# leo_SBM_BUCK.net
KiCad netlist of a schematic drawn in Altium Designer
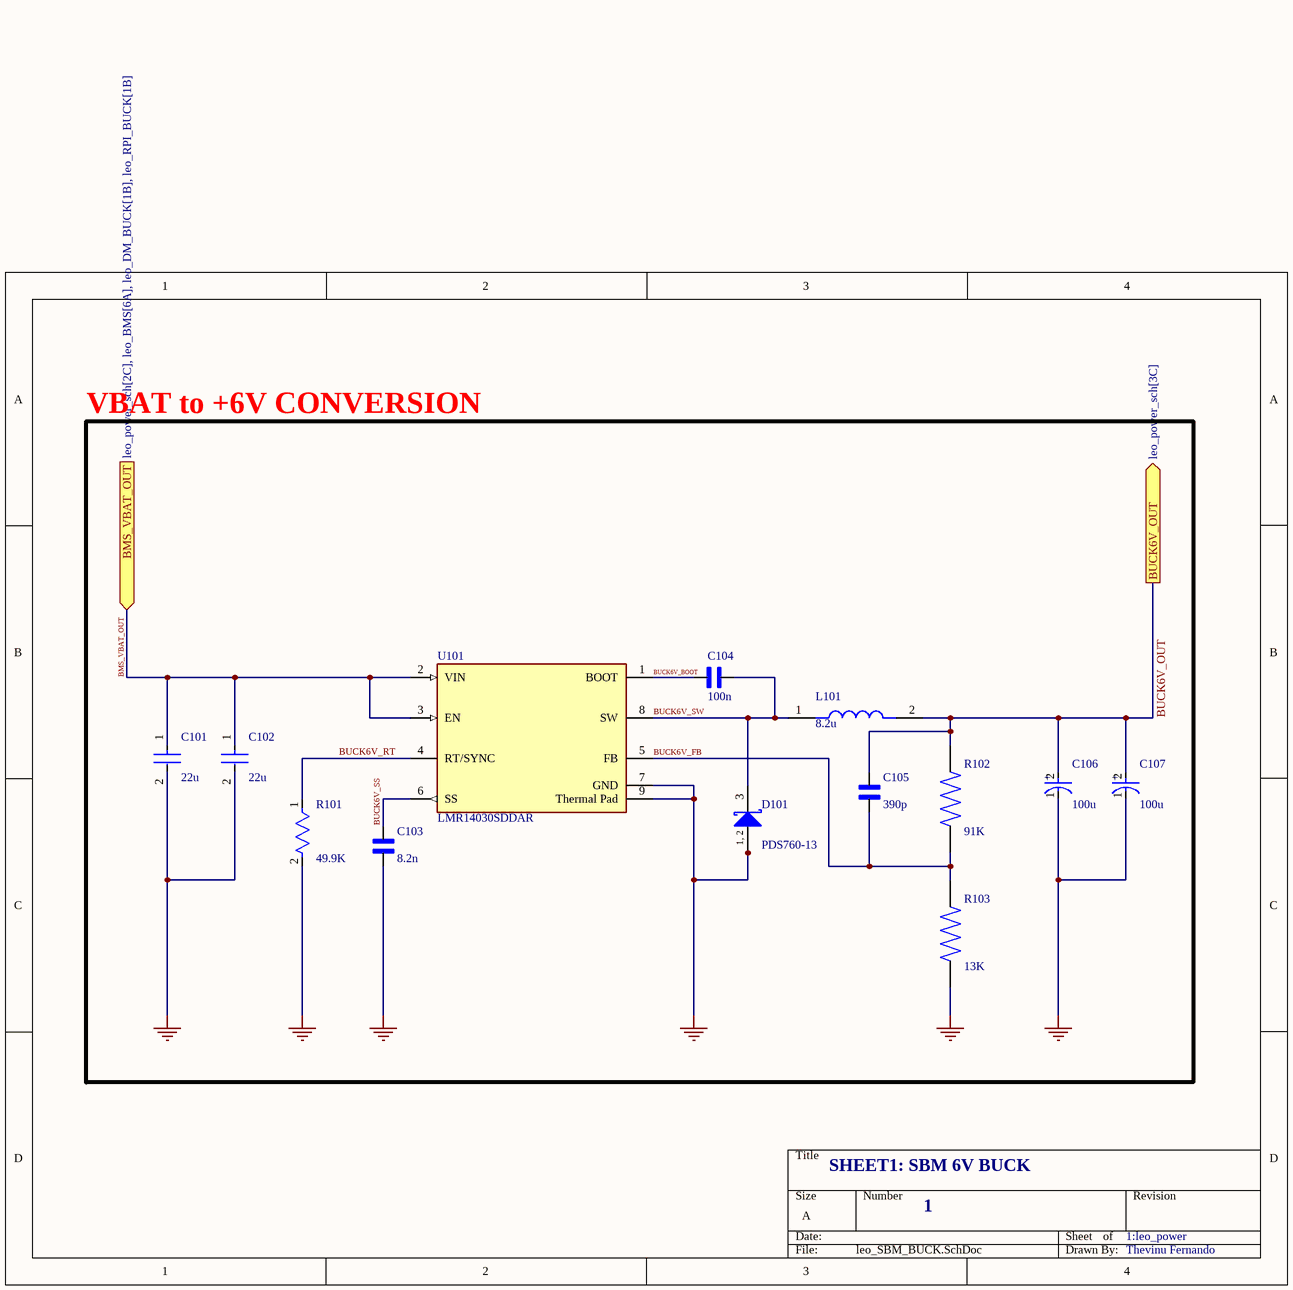
[diagram p0: leo_SBM_BUCK.SchDoc]

(export (version "E")
  (design (tool "Eeschema 10.0.6"))
  (components
    (comp (ref "C101")
      (value "22u")
      (footprint "CAP_1206")
      (fields
        (field (name "MOUSER PART NUMBER") "187-CL31A226KAHNNNE")
        (field (name "PART NUMBER") "CL31A226KAHNNNE")
        (field (name "DIGIKEY PART NUMBER") "1276-3047-1-ND")
      )
      (libsource (lib "leo_power_schlib") (part "CAP_1206"))
    )
    (comp (ref "C102")
      (value "22u")
      (footprint "CAP_1206")
      (fields
        (field (name "MOUSER PART NUMBER") "187-CL31A226KAHNNNE")
        (field (name "PART NUMBER") "CL31A226KAHNNNE")
        (field (name "DIGIKEY PART NUMBER") "1276-3047-1-ND")
      )
      (libsource (lib "leo_power_schlib") (part "CAP_1206"))
    )
    (comp (ref "C103")
      (value "8.2n")
      (footprint "CAP_0402")
      (description "±10% 50V Ceramic Capacitor X7R 0402")
      (fields (field (name "MF") "Samsung") (field (name "MP") "CL05B104KO5NNNC"))
      (libsource (lib "") (part "CAP_0402_1"))
    )
    (comp (ref "C104")
      (value "100n")
      (footprint "CAP_0402")
      (description "±10% 50V Ceramic Capacitor X7R 0402")
      (fields (field (name "MF") "Samsung") (field (name "MP") "CL05B104KO5NNNC"))
      (libsource (lib "leo_power_schlib") (part "CAP_0402"))
    )
    (comp (ref "C105")
      (value "390p")
      (footprint "CAP_0402")
      (description "±10% 50V Ceramic Capacitor X7R 0402")
      (fields (field (name "MF") "Samsung") (field (name "MP") "CL05B104KO5NNNC"))
      (libsource (lib "") (part "CAP_0402_1"))
    )
    (comp (ref "C106")
      (value "100u")
      (footprint "FP-OS-CON-SMT-C6-MFG")
      (description "100uF ±20% 16V Aluminum - Polymer Capacitors SMD,D6.3xL5.9mm 2000hrs@105℃")
      (fields (field (name "VOLTAGE") "16V") (field (name "TOLERANCE") "20%"))
      (libsource (lib "leo_power_schlib") (part "16SVPC100M"))
    )
    (comp (ref "C107")
      (value "100u")
      (footprint "FP-OS-CON-SMT-C6-MFG")
      (description "100uF ±20% 16V Aluminum - Polymer Capacitors SMD,D6.3xL5.9mm 2000hrs@105℃")
      (fields (field (name "VOLTAGE") "16V") (field (name "TOLERANCE") "20%"))
      (libsource (lib "leo_power_schlib") (part "16SVPC100M"))
    )
    (comp (ref "D101")
      (value "PDS760-13")
      (footprint "DIOD-POWERDI5-3_V")
      (description "Schottky Barrier Rectifier, 60 V, 7 A, -65 to 150 degC, 3-Pin SMD, RoHS, Tape and Reel")
      (fields (field (name "MANUFACTURER") "Diodes Inc"))
      (libsource (lib "leo_power_schlib") (part "PDS760-13"))
    )
    (comp (ref "L101")
      (value "8.2u")
      (footprint "IND_104CDMCCDS-8R2MC")
      (description "Inductor Power Shielded/Molded Wirewound 8.2uH 20% 100KHz Metal 8.3A 0.027Ohm DCR 4040 T/R")
      (fields (field (name "MF") "Sumida") (field (name "MP") "104CDMCCDS-8R2MC"))
      (libsource (lib "leo_power_schlib") (part "104CDMCCDS-8R2MC"))
    )
    (comp (ref "R101")
      (value "49.9K")
      (footprint "RES_0805")
      (description "49.9kΩ ±0.1% 125mW 0805 Thin Film Resistor AEC-Q200")
      (fields (field (name "TOLERANCE") "0.1%"))
      (libsource (lib "leo_power_schlib") (part "RES_0805"))
    )
    (comp (ref "R102")
      (value "91K")
      (footprint "RES_0603")
      (description "Â±1% 0.1W, 1/10W Chip Resistor 0603 (1608 Metric) Moisture Resistant Thick Film")
      (fields (field (name "MF") "Yageo") (field (name "MP") "RC0603FR-0791KL"))
      (libsource (lib "leo_power_schlib") (part "RES_0603"))
    )
    (comp (ref "R103")
      (value "13K")
      (footprint "RES_0603")
      (description "Â±1% 0.1W, 1/10W Chip Resistor 0603 (1608 Metric) Moisture Resistant Thick Film")
      (fields (field (name "MF") "Yageo") (field (name "MP") "RC0603FR-0791KL"))
      (libsource (lib "leo_power_schlib") (part "RES_0603"))
    )
    (comp (ref "U101")
      (value "LMR14030SDDAR")
      (footprint "FP-DDA0008E-MFG")
      (description "IC REG BUCK ADJ 3.5A 8SOPWR")
      (fields
        (field (name "OCTOPART") "https://octopart.com/lmr14030sddar-texas+instruments-55347267")
        (field (name "MANUFACTURER") "Texas Instruments")
      )
      (libsource (lib "leo_power_schlib") (part "LMR14030SDDAR"))
    )
  )
  (nets
    (net (code "1") (name "/BMS_VBAT_OUT") (class "Default")
      (node (ref "C101") (pin "1") (pinfunction "1_1") (pintype "passive"))
      (node (ref "C102") (pin "1") (pinfunction "1_1") (pintype "passive"))
      (node (ref "U101") (pin "2") (pinfunction "VIN_2") (pintype "input"))
      (node (ref "U101") (pin "3") (pinfunction "EN_3") (pintype "input"))
    )
    (net (code "2") (name "/BUCK6V_BOOT") (class "Default")
      (node (ref "C104") (pin "2") (pinfunction "2_2") (pintype "passive"))
      (node (ref "U101") (pin "1") (pinfunction "BOOT_1") (pintype "passive"))
    )
    (net (code "3") (name "/BUCK6V_FB") (class "Default")
      (node (ref "C105") (pin "1") (pinfunction "1_1") (pintype "passive"))
      (node (ref "R102") (pin "1") (pinfunction "1_1") (pintype "passive"))
      (node (ref "R103") (pin "2") (pinfunction "2_2") (pintype "passive"))
      (node (ref "U101") (pin "5") (pinfunction "FB_5") (pintype "passive"))
    )
    (net (code "4") (name "/BUCK6V_OUT") (class "Default")
      (node (ref "C105") (pin "2") (pinfunction "2_2") (pintype "passive"))
      (node (ref "C106") (pin "2") (pinfunction "A_2") (pintype "passive"))
      (node (ref "C107") (pin "2") (pinfunction "A_2") (pintype "passive"))
      (node (ref "L101") (pin "2") (pinfunction "2_2") (pintype "passive"))
      (node (ref "R102") (pin "2") (pinfunction "2_2") (pintype "passive"))
    )
    (net (code "5") (name "/BUCK6V_RT") (class "Default")
      (node (ref "R101") (pin "1") (pinfunction "1_1") (pintype "passive"))
      (node (ref "U101") (pin "4") (pinfunction "RT/SYNC_4") (pintype "passive"))
    )
    (net (code "6") (name "/BUCK6V_SS") (class "Default")
      (node (ref "C103") (pin "2") (pinfunction "2_2") (pintype "passive"))
      (node (ref "U101") (pin "6") (pinfunction "SS_6") (pintype "output"))
    )
    (net (code "7") (name "/BUCK6V_SW") (class "Default")
      (node (ref "C104") (pin "1") (pinfunction "1_1") (pintype "passive"))
      (node (ref "D101") (pin "3") (pinfunction "K_3") (pintype "passive"))
      (node (ref "L101") (pin "1") (pinfunction "1_1") (pintype "passive"))
      (node (ref "U101") (pin "8") (pinfunction "SW_8") (pintype "passive"))
    )
    (net (code "8") (name "GND") (class "Default")
      (node (ref "C101") (pin "2") (pinfunction "2_2") (pintype "passive"))
      (node (ref "C102") (pin "2") (pinfunction "2_2") (pintype "passive"))
      (node (ref "C103") (pin "1") (pinfunction "1_1") (pintype "passive"))
      (node (ref "C106") (pin "1") (pinfunction "C_1") (pintype "passive"))
      (node (ref "C107") (pin "1") (pinfunction "C_1") (pintype "passive"))
      (node (ref "D101") (pin "1") (pinfunction "A_1") (pintype "passive"))
      (node (ref "D101") (pin "2") (pinfunction "A_2") (pintype "passive"))
      (node (ref "R101") (pin "2") (pinfunction "2_2") (pintype "passive"))
      (node (ref "R103") (pin "1") (pinfunction "1_1") (pintype "passive"))
      (node (ref "U101") (pin "7") (pinfunction "GND_7") (pintype "power_in"))
      (node (ref "U101") (pin "9") (pinfunction "Thermal_Pad_9") (pintype "power_in"))
    )
  )
)
